# main.net
KiCad netlist of a schematic drawn in EAGLE
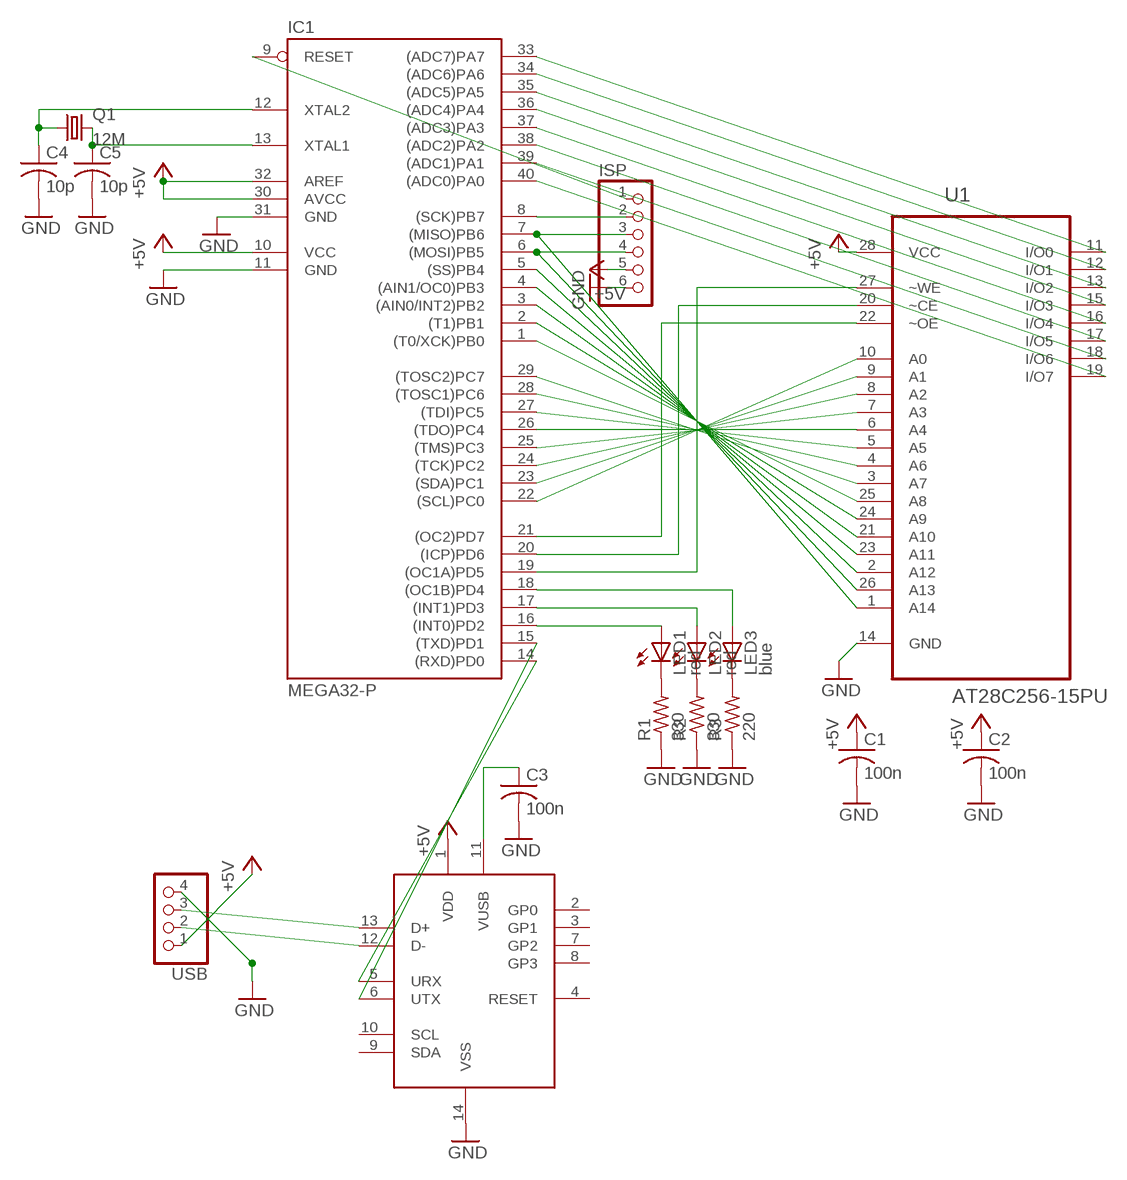
[diagram p0: schematic, sheet 1]

(export (version "E")
  (design (tool "Eeschema 10.0.6"))
  (components
    (comp (ref "BR1")
      (value "MCP2221A")
      (footprint "eagle-import:DIP14")
      (libsource (lib "eagle-import") (part "MCP2221A"))
    )
    (comp (ref "C1")
      (value "100n")
      (footprint "eagle-import:C0603")
      (libsource (lib "eagle-import") (part "C-USC0603"))
    )
    (comp (ref "C2")
      (value "100n")
      (footprint "eagle-import:C0603")
      (libsource (lib "eagle-import") (part "C-USC0603"))
    )
    (comp (ref "C3")
      (value "100n")
      (footprint "eagle-import:C0603")
      (libsource (lib "eagle-import") (part "C-USC0603"))
    )
    (comp (ref "C4")
      (value "10p")
      (footprint "eagle-import:C0603")
      (libsource (lib "eagle-import") (part "C-USC0603"))
    )
    (comp (ref "C5")
      (value "10p")
      (footprint "eagle-import:C0603")
      (libsource (lib "eagle-import") (part "C-USC0603"))
    )
    (comp (ref "IC1")
      (value "MEGA32-P")
      (footprint "eagle-import:DIL40")
      (fields (field (name "MPN") "ATMEGA32-16PU"))
      (libsource (lib "eagle-import") (part "MEGA32-P"))
    )
    (comp (ref "ISP")
      (value "PINHD-1X6")
      (footprint "eagle-import:1X06")
      (libsource (lib "eagle-import") (part "PINHD-1X6"))
    )
    (comp (ref "LED1")
      (value "red")
      (footprint "eagle-import:LED5MM")
      (libsource (lib "eagle-import") (part "LED5MM"))
    )
    (comp (ref "LED2")
      (value "red")
      (footprint "eagle-import:LED5MM")
      (libsource (lib "eagle-import") (part "LED5MM"))
    )
    (comp (ref "LED3")
      (value "blue")
      (footprint "eagle-import:LED5MM")
      (libsource (lib "eagle-import") (part "LED5MM"))
    )
    (comp (ref "Q1")
      (value "12M")
      (footprint "eagle-import:HC49_S")
      (libsource (lib "eagle-import") (part "CRYSTALHC49S"))
    )
    (comp (ref "R1")
      (value "330")
      (footprint "eagle-import:R0805")
      (libsource (lib "eagle-import") (part "R-US_R0805"))
    )
    (comp (ref "R2")
      (value "330")
      (footprint "eagle-import:R0805")
      (libsource (lib "eagle-import") (part "R-US_R0805"))
    )
    (comp (ref "R3")
      (value "220")
      (footprint "eagle-import:R0805")
      (libsource (lib "eagle-import") (part "R-US_R0805"))
    )
    (comp (ref "U1")
      (value "AT28C256-15PU")
      (footprint "eagle-import:DIP254P1524X482-28")
      (libsource (lib "eagle-import") (part "AT28C256-15PU"))
    )
    (comp (ref "USB")
      (value "PINHD-1X4")
      (footprint "eagle-import:1X04")
      (libsource (lib "eagle-import") (part "PINHD-1X4"))
    )
  )
  (nets
    (net (code "1") (name "+5V") (class "Default")
      (node (ref "BR1") (pin "1") (pinfunction "VDD_1") (pintype "bidirectional"))
      (node (ref "C1") (pin "1") (pinfunction "1_1") (pintype "passive"))
      (node (ref "C2") (pin "1") (pinfunction "1_1") (pintype "passive"))
      (node (ref "IC1") (pin "10") (pinfunction "VCC_10") (pintype "power_in"))
      (node (ref "IC1") (pin "30") (pinfunction "AVCC_30") (pintype "power_in"))
      (node (ref "IC1") (pin "32") (pinfunction "AREF_32") (pintype "passive"))
      (node (ref "ISP") (pin "5") (pinfunction "5_5") (pintype "passive"))
      (node (ref "U1") (pin "28") (pinfunction "VCC_28") (pintype "power_in"))
      (node (ref "USB") (pin "1") (pinfunction "1_1") (pintype "passive"))
    )
    (net (code "2") (name "GND") (class "Default")
      (node (ref "BR1") (pin "14") (pinfunction "VSS_14") (pintype "bidirectional"))
      (node (ref "C1") (pin "2") (pinfunction "2_2") (pintype "passive"))
      (node (ref "C2") (pin "2") (pinfunction "2_2") (pintype "passive"))
      (node (ref "C3") (pin "2") (pinfunction "2_2") (pintype "passive"))
      (node (ref "C4") (pin "2") (pinfunction "2_2") (pintype "passive"))
      (node (ref "C5") (pin "2") (pinfunction "2_2") (pintype "passive"))
      (node (ref "IC1") (pin "11") (pinfunction "GND_11") (pintype "power_in"))
      (node (ref "IC1") (pin "31") (pinfunction "GND_31") (pintype "power_in"))
      (node (ref "ISP") (pin "6") (pinfunction "6_6") (pintype "passive"))
      (node (ref "R1") (pin "1") (pinfunction "1_1") (pintype "passive"))
      (node (ref "R2") (pin "1") (pinfunction "1_1") (pintype "passive"))
      (node (ref "R3") (pin "1") (pinfunction "1_1") (pintype "passive"))
      (node (ref "U1") (pin "14") (pinfunction "GND_14") (pintype "passive"))
      (node (ref "USB") (pin "4") (pinfunction "4_4") (pintype "passive"))
    )
    (net (code "3") (name "Net-(BR1-D+)") (class "Default")
      (node (ref "BR1") (pin "13") (pinfunction "D+_13") (pintype "bidirectional"))
      (node (ref "USB") (pin "3") (pinfunction "3_3") (pintype "passive"))
    )
    (net (code "4") (name "Net-(BR1-D-)") (class "Default")
      (node (ref "BR1") (pin "12") (pinfunction "D-_12") (pintype "bidirectional"))
      (node (ref "USB") (pin "2") (pinfunction "2_2") (pintype "passive"))
    )
    (net (code "5") (name "Net-(BR1-URX)") (class "Default")
      (node (ref "BR1") (pin "5") (pinfunction "URX_5") (pintype "bidirectional"))
      (node (ref "IC1") (pin "14") (pinfunction "(RXD)PD0_14") (pintype "bidirectional"))
    )
    (net (code "6") (name "Net-(BR1-UTX)") (class "Default")
      (node (ref "BR1") (pin "6") (pinfunction "UTX_6") (pintype "bidirectional"))
      (node (ref "IC1") (pin "15") (pinfunction "(TXD)PD1_15") (pintype "bidirectional"))
    )
    (net (code "7") (name "Net-(BR1-VUSB)") (class "Default")
      (node (ref "BR1") (pin "11") (pinfunction "VUSB_11") (pintype "bidirectional"))
      (node (ref "C3") (pin "1") (pinfunction "1_1") (pintype "passive"))
    )
    (net (code "8") (name "Net-(IC1-(ADC0)PA0)") (class "Default")
      (node (ref "IC1") (pin "40") (pinfunction "(ADC0)PA0_40") (pintype "bidirectional"))
      (node (ref "U1") (pin "19") (pinfunction "I/O7_19") (pintype "bidirectional"))
    )
    (net (code "9") (name "Net-(IC1-(ADC1)PA1)") (class "Default")
      (node (ref "IC1") (pin "39") (pinfunction "(ADC1)PA1_39") (pintype "bidirectional"))
      (node (ref "U1") (pin "18") (pinfunction "I/O6_18") (pintype "bidirectional"))
    )
    (net (code "10") (name "Net-(IC1-(ADC2)PA2)") (class "Default")
      (node (ref "IC1") (pin "38") (pinfunction "(ADC2)PA2_38") (pintype "bidirectional"))
      (node (ref "U1") (pin "17") (pinfunction "I/O5_17") (pintype "bidirectional"))
    )
    (net (code "11") (name "Net-(IC1-(ADC3)PA3)") (class "Default")
      (node (ref "IC1") (pin "37") (pinfunction "(ADC3)PA3_37") (pintype "bidirectional"))
      (node (ref "U1") (pin "16") (pinfunction "I/O4_16") (pintype "bidirectional"))
    )
    (net (code "12") (name "Net-(IC1-(ADC4)PA4)") (class "Default")
      (node (ref "IC1") (pin "36") (pinfunction "(ADC4)PA4_36") (pintype "bidirectional"))
      (node (ref "U1") (pin "15") (pinfunction "I/O3_15") (pintype "bidirectional"))
    )
    (net (code "13") (name "Net-(IC1-(ADC5)PA5)") (class "Default")
      (node (ref "IC1") (pin "35") (pinfunction "(ADC5)PA5_35") (pintype "bidirectional"))
      (node (ref "U1") (pin "13") (pinfunction "I/O2_13") (pintype "bidirectional"))
    )
    (net (code "14") (name "Net-(IC1-(ADC6)PA6)") (class "Default")
      (node (ref "IC1") (pin "34") (pinfunction "(ADC6)PA6_34") (pintype "bidirectional"))
      (node (ref "U1") (pin "12") (pinfunction "I/O1_12") (pintype "bidirectional"))
    )
    (net (code "15") (name "Net-(IC1-(ADC7)PA7)") (class "Default")
      (node (ref "IC1") (pin "33") (pinfunction "(ADC7)PA7_33") (pintype "bidirectional"))
      (node (ref "U1") (pin "11") (pinfunction "I/O0_11") (pintype "bidirectional"))
    )
    (net (code "16") (name "Net-(IC1-(AIN0{slash}INT2)PB2)") (class "Default")
      (node (ref "IC1") (pin "3") (pinfunction "(AIN0/INT2)PB2_3") (pintype "bidirectional"))
      (node (ref "U1") (pin "21") (pinfunction "A10_21") (pintype "input"))
    )
    (net (code "17") (name "Net-(IC1-(AIN1{slash}OC0)PB3)") (class "Default")
      (node (ref "IC1") (pin "4") (pinfunction "(AIN1/OC0)PB3_4") (pintype "bidirectional"))
      (node (ref "U1") (pin "23") (pinfunction "A11_23") (pintype "input"))
    )
    (net (code "18") (name "Net-(IC1-(ICP)PD6)") (class "Default")
      (node (ref "IC1") (pin "20") (pinfunction "(ICP)PD6_20") (pintype "bidirectional"))
      (node (ref "U1") (pin "20") (pinfunction "~{CE}_20") (pintype "input"))
    )
    (net (code "19") (name "Net-(IC1-(INT0)PD2)") (class "Default")
      (node (ref "IC1") (pin "16") (pinfunction "(INT0)PD2_16") (pintype "bidirectional"))
      (node (ref "LED1") (pin "A") (pinfunction "A_A") (pintype "passive"))
    )
    (net (code "20") (name "Net-(IC1-(INT1)PD3)") (class "Default")
      (node (ref "IC1") (pin "17") (pinfunction "(INT1)PD3_17") (pintype "bidirectional"))
      (node (ref "LED2") (pin "A") (pinfunction "A_A") (pintype "passive"))
    )
    (net (code "21") (name "Net-(IC1-(MISO)PB6)") (class "Default")
      (node (ref "IC1") (pin "7") (pinfunction "(MISO)PB6_7") (pintype "bidirectional"))
      (node (ref "ISP") (pin "3") (pinfunction "3_3") (pintype "passive"))
      (node (ref "U1") (pin "1") (pinfunction "A14_1") (pintype "input"))
    )
    (net (code "22") (name "Net-(IC1-(MOSI)PB5)") (class "Default")
      (node (ref "IC1") (pin "6") (pinfunction "(MOSI)PB5_6") (pintype "bidirectional"))
      (node (ref "ISP") (pin "4") (pinfunction "4_4") (pintype "passive"))
      (node (ref "U1") (pin "26") (pinfunction "A13_26") (pintype "input"))
    )
    (net (code "23") (name "Net-(IC1-(OC1A)PD5)") (class "Default")
      (node (ref "IC1") (pin "19") (pinfunction "(OC1A)PD5_19") (pintype "bidirectional"))
      (node (ref "U1") (pin "27") (pinfunction "~{WE}_27") (pintype "input"))
    )
    (net (code "24") (name "Net-(IC1-(OC1B)PD4)") (class "Default")
      (node (ref "IC1") (pin "18") (pinfunction "(OC1B)PD4_18") (pintype "bidirectional"))
      (node (ref "LED3") (pin "A") (pinfunction "A_A") (pintype "passive"))
    )
    (net (code "25") (name "Net-(IC1-(OC2)PD7)") (class "Default")
      (node (ref "IC1") (pin "21") (pinfunction "(OC2)PD7_21") (pintype "bidirectional"))
      (node (ref "U1") (pin "22") (pinfunction "~{OE}_22") (pintype "input"))
    )
    (net (code "26") (name "Net-(IC1-(SCK)PB7)") (class "Default")
      (node (ref "IC1") (pin "8") (pinfunction "(SCK)PB7_8") (pintype "bidirectional"))
      (node (ref "ISP") (pin "2") (pinfunction "2_2") (pintype "passive"))
    )
    (net (code "27") (name "Net-(IC1-(SCL)PC0)") (class "Default")
      (node (ref "IC1") (pin "22") (pinfunction "(SCL)PC0_22") (pintype "bidirectional"))
      (node (ref "U1") (pin "10") (pinfunction "A0_10") (pintype "input"))
    )
    (net (code "28") (name "Net-(IC1-(SDA)PC1)") (class "Default")
      (node (ref "IC1") (pin "23") (pinfunction "(SDA)PC1_23") (pintype "bidirectional"))
      (node (ref "U1") (pin "9") (pinfunction "A1_9") (pintype "input"))
    )
    (net (code "29") (name "Net-(IC1-(SS)PB4)") (class "Default")
      (node (ref "IC1") (pin "5") (pinfunction "(SS)PB4_5") (pintype "bidirectional"))
      (node (ref "U1") (pin "2") (pinfunction "A12_2") (pintype "input"))
    )
    (net (code "30") (name "Net-(IC1-(T0{slash}XCK)PB0)") (class "Default")
      (node (ref "IC1") (pin "1") (pinfunction "(T0/XCK)PB0_1") (pintype "bidirectional"))
      (node (ref "U1") (pin "25") (pinfunction "A8_25") (pintype "input"))
    )
    (net (code "31") (name "Net-(IC1-(T1)PB1)") (class "Default")
      (node (ref "IC1") (pin "2") (pinfunction "(T1)PB1_2") (pintype "bidirectional"))
      (node (ref "U1") (pin "24") (pinfunction "A9_24") (pintype "input"))
    )
    (net (code "32") (name "Net-(IC1-(TCK)PC2)") (class "Default")
      (node (ref "IC1") (pin "24") (pinfunction "(TCK)PC2_24") (pintype "bidirectional"))
      (node (ref "U1") (pin "8") (pinfunction "A2_8") (pintype "input"))
    )
    (net (code "33") (name "Net-(IC1-(TDI)PC5)") (class "Default")
      (node (ref "IC1") (pin "27") (pinfunction "(TDI)PC5_27") (pintype "bidirectional"))
      (node (ref "U1") (pin "5") (pinfunction "A5_5") (pintype "input"))
    )
    (net (code "34") (name "Net-(IC1-(TDO)PC4)") (class "Default")
      (node (ref "IC1") (pin "26") (pinfunction "(TDO)PC4_26") (pintype "bidirectional"))
      (node (ref "U1") (pin "6") (pinfunction "A4_6") (pintype "input"))
    )
    (net (code "35") (name "Net-(IC1-(TMS)PC3)") (class "Default")
      (node (ref "IC1") (pin "25") (pinfunction "(TMS)PC3_25") (pintype "bidirectional"))
      (node (ref "U1") (pin "7") (pinfunction "A3_7") (pintype "input"))
    )
    (net (code "36") (name "Net-(IC1-(TOSC1)PC6)") (class "Default")
      (node (ref "IC1") (pin "28") (pinfunction "(TOSC1)PC6_28") (pintype "bidirectional"))
      (node (ref "U1") (pin "4") (pinfunction "A6_4") (pintype "input"))
    )
    (net (code "37") (name "Net-(IC1-(TOSC2)PC7)") (class "Default")
      (node (ref "IC1") (pin "29") (pinfunction "(TOSC2)PC7_29") (pintype "bidirectional"))
      (node (ref "U1") (pin "3") (pinfunction "A7_3") (pintype "input"))
    )
    (net (code "38") (name "Net-(IC1-RESET)") (class "Default")
      (node (ref "IC1") (pin "9") (pinfunction "RESET_9") (pintype "input"))
      (node (ref "ISP") (pin "1") (pinfunction "1_1") (pintype "passive"))
    )
    (net (code "39") (name "Net-(IC1-XTAL1)") (class "Default")
      (node (ref "C5") (pin "1") (pinfunction "1_1") (pintype "passive"))
      (node (ref "IC1") (pin "13") (pinfunction "XTAL1_13") (pintype "bidirectional"))
      (node (ref "Q1") (pin "2") (pinfunction "2_2") (pintype "passive"))
    )
    (net (code "40") (name "Net-(IC1-XTAL2)") (class "Default")
      (node (ref "C4") (pin "1") (pinfunction "1_1") (pintype "passive"))
      (node (ref "IC1") (pin "12") (pinfunction "XTAL2_12") (pintype "bidirectional"))
      (node (ref "Q1") (pin "1") (pinfunction "1_1") (pintype "passive"))
    )
    (net (code "41") (name "Net-(LED1-C)") (class "Default")
      (node (ref "LED1") (pin "K") (pinfunction "C_K") (pintype "passive"))
      (node (ref "R1") (pin "2") (pinfunction "2_2") (pintype "passive"))
    )
    (net (code "42") (name "Net-(LED2-C)") (class "Default")
      (node (ref "LED2") (pin "K") (pinfunction "C_K") (pintype "passive"))
      (node (ref "R2") (pin "2") (pinfunction "2_2") (pintype "passive"))
    )
    (net (code "43") (name "Net-(LED3-C)") (class "Default")
      (node (ref "LED3") (pin "K") (pinfunction "C_K") (pintype "passive"))
      (node (ref "R3") (pin "2") (pinfunction "2_2") (pintype "passive"))
    )
    (net (code "44") (name "unconnected-(BR1-GP0-Pad2)") (class "Default")
      (node (ref "BR1") (pin "2") (pinfunction "GP0_2") (pintype "bidirectional"))
    )
    (net (code "45") (name "unconnected-(BR1-GP1-Pad3)") (class "Default")
      (node (ref "BR1") (pin "3") (pinfunction "GP1_3") (pintype "bidirectional"))
    )
    (net (code "46") (name "unconnected-(BR1-GP2-Pad7)") (class "Default")
      (node (ref "BR1") (pin "7") (pinfunction "GP2_7") (pintype "bidirectional"))
    )
    (net (code "47") (name "unconnected-(BR1-GP3-Pad8)") (class "Default")
      (node (ref "BR1") (pin "8") (pinfunction "GP3_8") (pintype "bidirectional"))
    )
    (net (code "48") (name "unconnected-(BR1-RESET-Pad4)") (class "Default")
      (node (ref "BR1") (pin "4") (pinfunction "RESET_4") (pintype "bidirectional"))
    )
    (net (code "49") (name "unconnected-(BR1-SCL-Pad10)") (class "Default")
      (node (ref "BR1") (pin "10") (pinfunction "SCL_10") (pintype "bidirectional"))
    )
    (net (code "50") (name "unconnected-(BR1-SDA-Pad9)") (class "Default")
      (node (ref "BR1") (pin "9") (pinfunction "SDA_9") (pintype "bidirectional"))
    )
  )
)
